# untitled.net
KiCad netlist of a schematic drawn in EAGLE
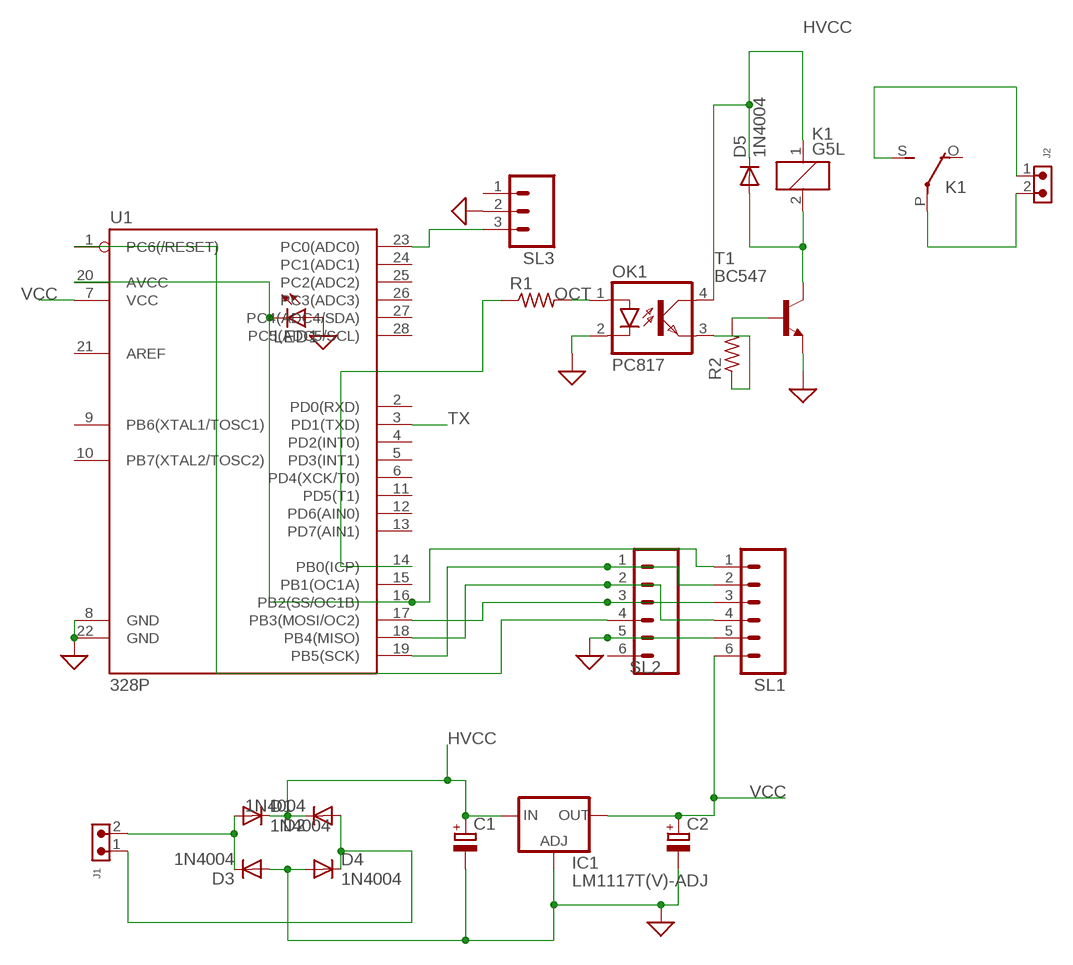
[diagram p0: schematic, sheet 1]

(export (version "E")
  (design (tool "Eeschema 10.0.6"))
  (components
    (comp (ref "C1")
      (value "CPOL-EUE5-10.5")
      (footprint "eagle-import:E5-10,5")
      (libsource (lib "eagle-import") (part "CPOL-EUE5-10.5"))
    )
    (comp (ref "C2")
      (value "CPOL-EUE5-10.5")
      (footprint "eagle-import:E5-10,5")
      (libsource (lib "eagle-import") (part "CPOL-EUE5-10.5"))
    )
    (comp (ref "D1")
      (value "1N4004")
      (footprint "eagle-import:DO41-10")
      (libsource (lib "eagle-import") (part "1N4004"))
    )
    (comp (ref "D2")
      (value "1N4004")
      (footprint "eagle-import:DO41-10")
      (libsource (lib "eagle-import") (part "1N4004"))
    )
    (comp (ref "D3")
      (value "1N4004")
      (footprint "eagle-import:DO41-10")
      (libsource (lib "eagle-import") (part "1N4004"))
    )
    (comp (ref "D4")
      (value "1N4004")
      (footprint "eagle-import:DO41-10")
      (libsource (lib "eagle-import") (part "1N4004"))
    )
    (comp (ref "D5")
      (value "1N4004")
      (footprint "eagle-import:DO41-10")
      (libsource (lib "eagle-import") (part "1N4004"))
    )
    (comp (ref "IC1")
      (value "LM1117T(V)-ADJ")
      (footprint "eagle-import:TO220V")
      (fields (field (name "MF") "Texas Instruments") (field (name "MPN") "LM1777T-ADJ"))
      (libsource (lib "eagle-import") (part "LM1117?-ADJT(V)"))
    )
    (comp (ref "J1")
      (value "691305530002")
      (footprint "eagle-import:691305530002")
      (libsource (lib "eagle-import") (part "691305530002"))
    )
    (comp (ref "J2")
      (value "691305530002")
      (footprint "eagle-import:691305530002")
      (libsource (lib "eagle-import") (part "691305530002"))
    )
    (comp (ref "K1")
      (value "G5L")
      (footprint "eagle-import:G5LE")
      (libsource (lib "eagle-import") (part "G5L"))
    )
    (comp (ref "LED1")
      (value "LED5MM")
      (footprint "eagle-import:LED5MM")
      (libsource (lib "eagle-import") (part "LED5MM"))
    )
    (comp (ref "OK1")
      (value "PC817")
      (footprint "eagle-import:DIL04")
      (fields (field (name "MPN") "PC817X4J000F"))
      (libsource (lib "eagle-import") (part "PC817"))
    )
    (comp (ref "R1")
      (value "R-US_0207/10")
      (footprint "eagle-import:0207_10")
      (libsource (lib "eagle-import") (part "R-US_0207/10"))
    )
    (comp (ref "R2")
      (value "R-US_0207/10")
      (footprint "eagle-import:0207_10")
      (libsource (lib "eagle-import") (part "R-US_0207/10"))
    )
    (comp (ref "SL1")
      (value "M06")
      (footprint "eagle-import:06P")
      (libsource (lib "eagle-import") (part "M06"))
    )
    (comp (ref "SL2")
      (value "M06")
      (footprint "eagle-import:06P")
      (libsource (lib "eagle-import") (part "M06"))
    )
    (comp (ref "SL3")
      (value "M03")
      (footprint "eagle-import:03P")
      (libsource (lib "eagle-import") (part "M03"))
    )
    (comp (ref "T1")
      (value "BC547")
      (footprint "eagle-import:TO92")
      (libsource (lib "eagle-import") (part "BC547"))
    )
    (comp (ref "U1")
      (value "328P")
      (footprint "eagle-import:DIP28")
      (libsource (lib "eagle-import") (part "ATMEGA328P_PDIP"))
    )
  )
  (nets
    (net (code "1") (name "/HVCC") (class "Default")
      (node (ref "C1") (pin "+") (pinfunction "+_+") (pintype "passive"))
      (node (ref "D1") (pin "C") (pinfunction "C_C") (pintype "passive"))
      (node (ref "D2") (pin "C") (pinfunction "C_C") (pintype "passive"))
      (node (ref "D5") (pin "C") (pinfunction "C_C") (pintype "passive"))
      (node (ref "IC1") (pin "3") (pinfunction "IN_3") (pintype "input"))
      (node (ref "K1") (pin "1") (pinfunction "1_1") (pintype "passive"))
      (node (ref "OK1") (pin "4") (pinfunction "COL_4") (pintype "passive"))
    )
    (net (code "2") (name "/OCT") (class "Default")
      (node (ref "OK1") (pin "1") (pinfunction "A_1") (pintype "passive"))
      (node (ref "R1") (pin "2") (pinfunction "2_2") (pintype "passive"))
    )
    (net (code "3") (name "/TX") (class "Default")
      (node (ref "U1") (pin "3") (pinfunction "PD1(TXD)_3") (pintype "bidirectional"))
    )
    (net (code "4") (name "/VCC") (class "Default")
      (node (ref "C2") (pin "+") (pinfunction "+_+") (pintype "passive"))
      (node (ref "IC1") (pin "2") (pinfunction "OUT_2") (pintype "passive"))
      (node (ref "SL1") (pin "6") (pinfunction "6_6") (pintype "passive"))
      (node (ref "U1") (pin "7") (pinfunction "VCC_7") (pintype "bidirectional"))
    )
    (net (code "5") (name "Net-(D1-PadA)") (class "Default")
      (node (ref "D1") (pin "A") (pinfunction "A_A") (pintype "passive"))
      (node (ref "D3") (pin "C") (pinfunction "C_C") (pintype "passive"))
      (node (ref "J1") (pin "2") (pinfunction "2_2") (pintype "passive"))
    )
    (net (code "6") (name "Net-(D2-PadA)") (class "Default")
      (node (ref "D2") (pin "A") (pinfunction "A_A") (pintype "passive"))
      (node (ref "D4") (pin "C") (pinfunction "C_C") (pintype "passive"))
      (node (ref "J1") (pin "1") (pinfunction "1_1") (pintype "passive"))
    )
    (net (code "7") (name "Net-(J2-Pad1)") (class "Default")
      (node (ref "J2") (pin "1") (pinfunction "1_1") (pintype "passive"))
      (node (ref "K1") (pin "S") (pinfunction "S_S") (pintype "passive"))
    )
    (net (code "8") (name "Net-(J2-Pad2)") (class "Default")
      (node (ref "J2") (pin "2") (pinfunction "2_2") (pintype "passive"))
      (node (ref "K1") (pin "P") (pinfunction "P_P") (pintype "passive"))
    )
    (net (code "9") (name "Net-(LED1-C)") (class "Default")
      (node (ref "LED1") (pin "K") (pinfunction "C_K") (pintype "passive"))
      (node (ref "SL1") (pin "1") (pinfunction "1_1") (pintype "passive"))
      (node (ref "U1") (pin "16") (pinfunction "PB2(SS/OC1B)_16") (pintype "bidirectional"))
      (node (ref "U1") (pin "20") (pinfunction "AVCC_20") (pintype "bidirectional"))
    )
    (net (code "10") (name "Net-(OK1-EMIT)") (class "Default")
      (node (ref "OK1") (pin "3") (pinfunction "EMIT_3") (pintype "passive"))
      (node (ref "R2") (pin "1") (pinfunction "1_1") (pintype "passive"))
    )
    (net (code "11") (name "Net-(T1-B)") (class "Default")
      (node (ref "R2") (pin "2") (pinfunction "2_2") (pintype "passive"))
      (node (ref "T1") (pin "2") (pinfunction "B_2") (pintype "passive"))
    )
    (net (code "12") (name "Net-(T1-C)") (class "Default")
      (node (ref "D5") (pin "A") (pinfunction "A_A") (pintype "passive"))
      (node (ref "K1") (pin "2") (pinfunction "2_2") (pintype "passive"))
      (node (ref "T1") (pin "3") (pinfunction "C_3") (pintype "passive"))
    )
    (net (code "13") (name "Net-(U1-PB0(ICP))") (class "Default")
      (node (ref "R1") (pin "1") (pinfunction "1_1") (pintype "passive"))
      (node (ref "U1") (pin "14") (pinfunction "PB0(ICP)_14") (pintype "bidirectional"))
    )
    (net (code "14") (name "Net-(U1-PB3(MOSI{slash}OC2))") (class "Default")
      (node (ref "SL1") (pin "3") (pinfunction "3_3") (pintype "passive"))
      (node (ref "SL2") (pin "3") (pinfunction "3_3") (pintype "passive"))
      (node (ref "U1") (pin "17") (pinfunction "PB3(MOSI/OC2)_17") (pintype "bidirectional"))
    )
    (net (code "15") (name "Net-(U1-PB4(MISO))") (class "Default")
      (node (ref "SL1") (pin "4") (pinfunction "4_4") (pintype "passive"))
      (node (ref "SL2") (pin "2") (pinfunction "2_2") (pintype "passive"))
      (node (ref "U1") (pin "18") (pinfunction "PB4(MISO)_18") (pintype "bidirectional"))
    )
    (net (code "16") (name "Net-(U1-PB5(SCK))") (class "Default")
      (node (ref "SL1") (pin "2") (pinfunction "2_2") (pintype "passive"))
      (node (ref "SL2") (pin "1") (pinfunction "1_1") (pintype "passive"))
      (node (ref "U1") (pin "19") (pinfunction "PB5(SCK)_19") (pintype "bidirectional"))
    )
    (net (code "17") (name "Net-(U1-PC0(ADC0))") (class "Default")
      (node (ref "SL3") (pin "3") (pinfunction "3_3") (pintype "passive"))
      (node (ref "U1") (pin "23") (pinfunction "PC0(ADC0)_23") (pintype "bidirectional"))
    )
    (net (code "18") (name "Net-(U1-PC6({slash}RESET))") (class "Default")
      (node (ref "SL2") (pin "4") (pinfunction "4_4") (pintype "passive"))
      (node (ref "U1") (pin "1") (pinfunction "PC6(/RESET)_1") (pintype "bidirectional"))
    )
    (net (code "19") (name "SUP") (class "Default")
      (node (ref "C1") (pin "-") (pinfunction "-_-") (pintype "passive"))
      (node (ref "C2") (pin "-") (pinfunction "-_-") (pintype "passive"))
      (node (ref "D3") (pin "A") (pinfunction "A_A") (pintype "passive"))
      (node (ref "D4") (pin "A") (pinfunction "A_A") (pintype "passive"))
      (node (ref "IC1") (pin "1") (pinfunction "ADJ_1") (pintype "input"))
      (node (ref "LED1") (pin "A") (pinfunction "A_A") (pintype "passive"))
      (node (ref "OK1") (pin "2") (pinfunction "C_2") (pintype "passive"))
      (node (ref "SL1") (pin "5") (pinfunction "5_5") (pintype "passive"))
      (node (ref "SL2") (pin "5") (pinfunction "5_5") (pintype "passive"))
      (node (ref "SL3") (pin "2") (pinfunction "2_2") (pintype "passive"))
      (node (ref "T1") (pin "1") (pinfunction "E_1") (pintype "passive"))
      (node (ref "U1") (pin "22") (pinfunction "GND_22") (pintype "bidirectional"))
      (node (ref "U1") (pin "8") (pinfunction "GND_8") (pintype "bidirectional"))
    )
    (net (code "20") (name "unconnected-(K1-PadO)") (class "Default")
      (node (ref "K1") (pin "O") (pinfunction "O_O") (pintype "passive"))
    )
    (net (code "21") (name "unconnected-(SL2-Pad6)") (class "Default")
      (node (ref "SL2") (pin "6") (pinfunction "6_6") (pintype "passive"))
    )
    (net (code "22") (name "unconnected-(SL3-Pad1)") (class "Default")
      (node (ref "SL3") (pin "1") (pinfunction "1_1") (pintype "passive"))
    )
    (net (code "23") (name "unconnected-(U1-AREF-Pad21)") (class "Default")
      (node (ref "U1") (pin "21") (pinfunction "AREF_21") (pintype "bidirectional"))
    )
    (net (code "24") (name "unconnected-(U1-PB1(OC1A)-Pad15)") (class "Default")
      (node (ref "U1") (pin "15") (pinfunction "PB1(OC1A)_15") (pintype "bidirectional"))
    )
    (net (code "25") (name "unconnected-(U1-PB6(XTAL1{slash}TOSC1)-Pad9)") (class "Default")
      (node (ref "U1") (pin "9") (pinfunction "PB6(XTAL1/TOSC1)_9") (pintype "bidirectional"))
    )
    (net (code "26") (name "unconnected-(U1-PB7(XTAL2{slash}TOSC2)-Pad10)") (class "Default")
      (node (ref "U1") (pin "10") (pinfunction "PB7(XTAL2/TOSC2)_10") (pintype "bidirectional"))
    )
    (net (code "27") (name "unconnected-(U1-PC1(ADC1)-Pad24)") (class "Default")
      (node (ref "U1") (pin "24") (pinfunction "PC1(ADC1)_24") (pintype "bidirectional"))
    )
    (net (code "28") (name "unconnected-(U1-PC2(ADC2)-Pad25)") (class "Default")
      (node (ref "U1") (pin "25") (pinfunction "PC2(ADC2)_25") (pintype "bidirectional"))
    )
    (net (code "29") (name "unconnected-(U1-PC3(ADC3)-Pad26)") (class "Default")
      (node (ref "U1") (pin "26") (pinfunction "PC3(ADC3)_26") (pintype "bidirectional"))
    )
    (net (code "30") (name "unconnected-(U1-PC4(ADC4{slash}SDA)-Pad27)") (class "Default")
      (node (ref "U1") (pin "27") (pinfunction "PC4(ADC4/SDA)_27") (pintype "bidirectional"))
    )
    (net (code "31") (name "unconnected-(U1-PC5(ADC5{slash}SCL)-Pad28)") (class "Default")
      (node (ref "U1") (pin "28") (pinfunction "PC5(ADC5/SCL)_28") (pintype "bidirectional"))
    )
    (net (code "32") (name "unconnected-(U1-PD0(RXD)-Pad2)") (class "Default")
      (node (ref "U1") (pin "2") (pinfunction "PD0(RXD)_2") (pintype "bidirectional"))
    )
    (net (code "33") (name "unconnected-(U1-PD2(INT0)-Pad4)") (class "Default")
      (node (ref "U1") (pin "4") (pinfunction "PD2(INT0)_4") (pintype "bidirectional"))
    )
    (net (code "34") (name "unconnected-(U1-PD3(INT1)-Pad5)") (class "Default")
      (node (ref "U1") (pin "5") (pinfunction "PD3(INT1)_5") (pintype "bidirectional"))
    )
    (net (code "35") (name "unconnected-(U1-PD4(XCK{slash}T0)-Pad6)") (class "Default")
      (node (ref "U1") (pin "6") (pinfunction "PD4(XCK/T0)_6") (pintype "bidirectional"))
    )
    (net (code "36") (name "unconnected-(U1-PD5(T1)-Pad11)") (class "Default")
      (node (ref "U1") (pin "11") (pinfunction "PD5(T1)_11") (pintype "bidirectional"))
    )
    (net (code "37") (name "unconnected-(U1-PD6(AIN0)-Pad12)") (class "Default")
      (node (ref "U1") (pin "12") (pinfunction "PD6(AIN0)_12") (pintype "bidirectional"))
    )
    (net (code "38") (name "unconnected-(U1-PD7(AIN1)-Pad13)") (class "Default")
      (node (ref "U1") (pin "13") (pinfunction "PD7(AIN1)_13") (pintype "bidirectional"))
    )
  )
)
